# CellsVoltMeasurementSensor.net
KiCad netlist of a schematic drawn in Altium Designer
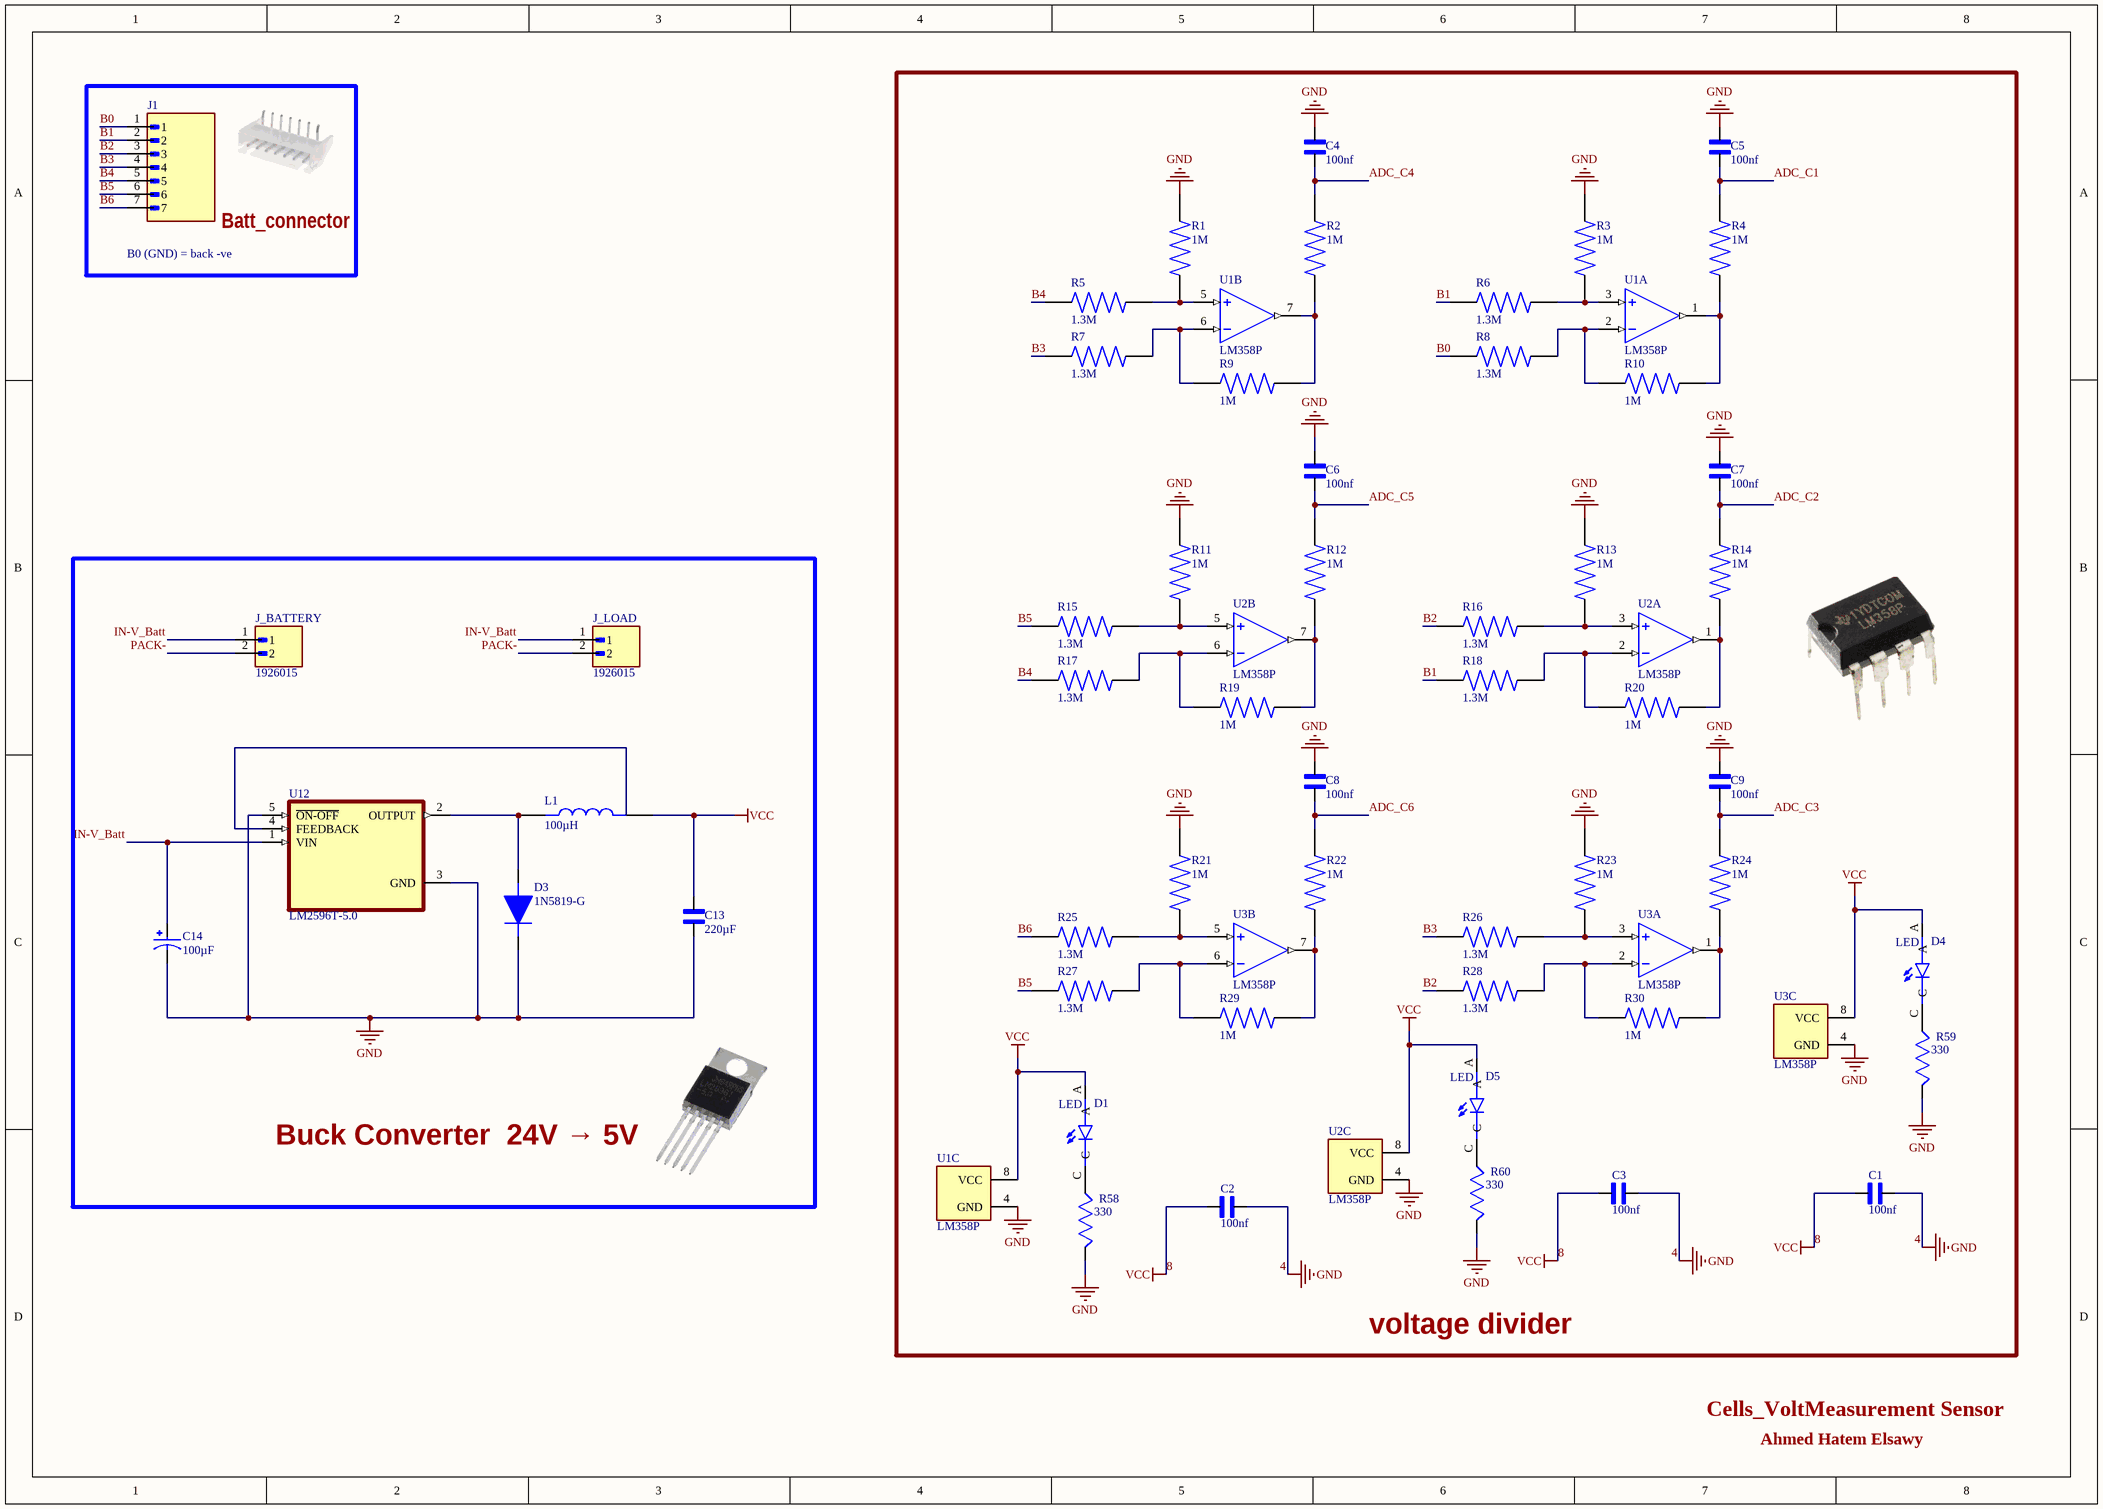
[diagram p0: CellsVoltMeasurementSensor.SchDoc]

(export (version "E")
  (design (tool "Eeschema 10.0.6"))
  (components
    (comp (ref "C1")
      (value "100nf")
      (footprint "CAPC1608X90N")
      (description "Capacitor MLCC 0603 100nF 50V ¦ AVX 06035C104K4T2A")
      (fields (field (name "MF") "AVX") (field (name "MP") "06035C104K4T2A"))
      (libsource (lib "") (part "06035C104K4T2A_1"))
    )
    (comp (ref "C2")
      (value "100nf")
      (footprint "CAPC1608X90N")
      (description "Capacitor MLCC 0603 100nF 50V ¦ AVX 06035C104K4T2A")
      (fields (field (name "MF") "AVX") (field (name "MP") "06035C104K4T2A"))
      (libsource (lib "") (part "06035C104K4T2A_1"))
    )
    (comp (ref "C3")
      (value "100nf")
      (footprint "CAPC1608X90N")
      (description "Capacitor MLCC 0603 100nF 50V ¦ AVX 06035C104K4T2A")
      (fields (field (name "MF") "AVX") (field (name "MP") "06035C104K4T2A"))
      (libsource (lib "") (part "06035C104K4T2A_1"))
    )
    (comp (ref "C4")
      (value "100nf")
      (footprint "CAPC1608X90N")
      (description "Capacitor MLCC 0603 100nF 50V ¦ AVX 06035C104K4T2A")
      (fields (field (name "MF") "AVX") (field (name "MP") "06035C104K4T2A"))
      (libsource (lib "06035C104K4T2A") (part "06035C104K4T2A"))
    )
    (comp (ref "C5")
      (value "100nf")
      (footprint "CAPC1608X90N")
      (description "Capacitor MLCC 0603 100nF 50V ¦ AVX 06035C104K4T2A")
      (fields (field (name "MF") "AVX") (field (name "MP") "06035C104K4T2A"))
      (libsource (lib "06035C104K4T2A") (part "06035C104K4T2A"))
    )
    (comp (ref "C6")
      (value "100nf")
      (footprint "CAPC1608X90N")
      (description "Capacitor MLCC 0603 100nF 50V ¦ AVX 06035C104K4T2A")
      (fields (field (name "MF") "AVX") (field (name "MP") "06035C104K4T2A"))
      (libsource (lib "06035C104K4T2A") (part "06035C104K4T2A"))
    )
    (comp (ref "C7")
      (value "100nf")
      (footprint "CAPC1608X90N")
      (description "Capacitor MLCC 0603 100nF 50V ¦ AVX 06035C104K4T2A")
      (fields (field (name "MF") "AVX") (field (name "MP") "06035C104K4T2A"))
      (libsource (lib "06035C104K4T2A") (part "06035C104K4T2A"))
    )
    (comp (ref "C8")
      (value "100nf")
      (footprint "CAPC1608X90N")
      (description "Capacitor MLCC 0603 100nF 50V ¦ AVX 06035C104K4T2A")
      (fields (field (name "MF") "AVX") (field (name "MP") "06035C104K4T2A"))
      (libsource (lib "06035C104K4T2A") (part "06035C104K4T2A"))
    )
    (comp (ref "C9")
      (value "100nf")
      (footprint "CAPC1608X90N")
      (description "Capacitor MLCC 0603 100nF 50V ¦ AVX 06035C104K4T2A")
      (fields (field (name "MF") "AVX") (field (name "MP") "06035C104K4T2A"))
      (libsource (lib "06035C104K4T2A") (part "06035C104K4T2A"))
    )
    (comp (ref "C13")
      (value "220µF")
      (footprint "CAPPM7343X310N")
      (description "Capacitor;Tantalum;220uF;Tol 10%;SMT;Vol-Rtg 10V;Size 7343-43 ¦ Sprague / Vishay 593D227X9010E2TE3")
      (fields (field (name "MF") "Vishay Sprague") (field (name "MP") "593D227X9010E2TE3"))
      (libsource (lib "593D227X9010E2TE3") (part "593D227X9010E2TE3"))
    )
    (comp (ref "C14")
      (value "100µF")
      (footprint "CAP_EEEFN1E101UP")
      (description "CAP ALUM 100UF 20% 25V SMD")
      (fields (field (name "MF") "Panasonic") (field (name "MP") "EEEFN1E101UP"))
      (libsource (lib "EEEFN1E101UP") (part "EEEFN1E101UP"))
    )
    (comp (ref "D1")
      (value "LED")
      (footprint "LED_WP7113ID")
      (description "Red 617nm LED Indication - Discrete 2V Radial")
      (fields (field (name "MP") "WP7113ID") (field (name "MF") "Kingbright"))
      (libsource (lib "WP7113ID") (part "WP7113ID"))
    )
    (comp (ref "D3")
      (value "1N5819-G")
      (footprint "DIOAD1405W75L465D235")
      (fields (field (name "MF") "ON Semiconductor") (field (name "MP") "1N5819G"))
      (libsource (lib "1N5819-G") (part "1N5819-G"))
    )
    (comp (ref "D4")
      (value "LED")
      (footprint "LED_WP7113ID")
      (description "Red 617nm LED Indication - Discrete 2V Radial")
      (fields (field (name "MP") "WP7113ID") (field (name "MF") "Kingbright"))
      (libsource (lib "WP7113ID") (part "WP7113ID"))
    )
    (comp (ref "D5")
      (value "LED")
      (footprint "LED_WP7113ID")
      (description "Red 617nm LED Indication - Discrete 2V Radial")
      (fields (field (name "MP") "WP7113ID") (field (name "MF") "Kingbright"))
      (libsource (lib "WP7113ID") (part "WP7113ID"))
    )
    (comp (ref "J1")
      (value "S7B-XH-A(LF)(SN)")
      (footprint "JST_S7B-XH-A(LF)(SN)")
      (description "Connector Header Through Hole, Right Angle 7 position 0.098 (2.50mm)")
      (fields (field (name "MF") "JST Sales"))
      (libsource (lib "S7B-XH-A_LF__SN_") (part "S7B-XH-A(LF)(SN)"))
    )
    (comp (ref "J_BATTERY")
      (value "1926015")
      (footprint "PHOENIX_1926015")
      (libsource (lib "1926015") (part "1926015"))
    )
    (comp (ref "J_LOAD")
      (value "1926015")
      (footprint "PHOENIX_1926015")
      (libsource (lib "1926015") (part "1926015"))
    )
    (comp (ref "L1")
      (value "100µH")
      (footprint "INDC2012X145N")
      (description "100ÂµH Shielded Multilayer Inductor 2mA 3.1Ohm Max 0805 (2012 Metric)")
      (fields (field (name "MF") "TDK") (field (name "MP") "MLF2012C101MTD25"))
      (libsource (lib "MLF2012C101MTD25") (part "MLF2012C101MTD25"))
    )
    (comp (ref "R1")
      (value "1M")
      (footprint "RESC3216X75N")
      (description "Res 1206 1M 1% 250mW ¦ Bourns CR1206-FX-1004ELF")
      (fields (field (name "MF") "Bourns") (field (name "MP") "CR1206-FX-1004ELF"))
      (libsource (lib "CR1206-FX-1004ELF") (part "CR1206-FX-1004ELF"))
    )
    (comp (ref "R2")
      (value "1M")
      (footprint "RESC3216X75N")
      (description "Res 1206 1M 1% 250mW ¦ Bourns CR1206-FX-1004ELF")
      (fields (field (name "MF") "Bourns") (field (name "MP") "CR1206-FX-1004ELF"))
      (libsource (lib "CR1206-FX-1004ELF") (part "CR1206-FX-1004ELF"))
    )
    (comp (ref "R3")
      (value "1M")
      (footprint "RESC3216X75N")
      (description "Res 1206 1M 1% 250mW ¦ Bourns CR1206-FX-1004ELF")
      (fields (field (name "MF") "Bourns") (field (name "MP") "CR1206-FX-1004ELF"))
      (libsource (lib "CR1206-FX-1004ELF") (part "CR1206-FX-1004ELF"))
    )
    (comp (ref "R4")
      (value "1M")
      (footprint "RESC3216X75N")
      (description "Res 1206 1M 1% 250mW ¦ Bourns CR1206-FX-1004ELF")
      (fields (field (name "MF") "Bourns") (field (name "MP") "CR1206-FX-1004ELF"))
      (libsource (lib "CR1206-FX-1004ELF") (part "CR1206-FX-1004ELF"))
    )
    (comp (ref "R5")
      (value "1.3M")
      (footprint "RESC5025X70N")
      (description "Res Thick Film 2010 1.3M Ohm 5% 3/4W -400ppm/Â°C to 150ppm/Â°C Molded SMD SMD Embossed Carrier T/R")
      (fields (field (name "MF") "Panasonic") (field (name "MP") "ERJ-12ZYJ135U"))
      (libsource (lib "ERJ-12ZYJ135U") (part "ERJ-12ZYJ135U"))
    )
    (comp (ref "R6")
      (value "1.3M")
      (footprint "RESC5025X70N")
      (description "Res Thick Film 2010 1.3M Ohm 5% 3/4W -400ppm/Â°C to 150ppm/Â°C Molded SMD SMD Embossed Carrier T/R")
      (fields (field (name "MF") "Panasonic") (field (name "MP") "ERJ-12ZYJ135U"))
      (libsource (lib "ERJ-12ZYJ135U") (part "ERJ-12ZYJ135U"))
    )
    (comp (ref "R7")
      (value "1.3M")
      (footprint "RESC5025X70N")
      (description "Res Thick Film 2010 1.3M Ohm 5% 3/4W -400ppm/Â°C to 150ppm/Â°C Molded SMD SMD Embossed Carrier T/R")
      (fields (field (name "MF") "Panasonic") (field (name "MP") "ERJ-12ZYJ135U"))
      (libsource (lib "ERJ-12ZYJ135U") (part "ERJ-12ZYJ135U"))
    )
    (comp (ref "R8")
      (value "1.3M")
      (footprint "RESC5025X70N")
      (description "Res Thick Film 2010 1.3M Ohm 5% 3/4W -400ppm/Â°C to 150ppm/Â°C Molded SMD SMD Embossed Carrier T/R")
      (fields (field (name "MF") "Panasonic") (field (name "MP") "ERJ-12ZYJ135U"))
      (libsource (lib "ERJ-12ZYJ135U") (part "ERJ-12ZYJ135U"))
    )
    (comp (ref "R9")
      (value "1M")
      (footprint "RESC3216X75N")
      (description "Res 1206 1M 1% 250mW ¦ Bourns CR1206-FX-1004ELF")
      (fields (field (name "MF") "Bourns") (field (name "MP") "CR1206-FX-1004ELF"))
      (libsource (lib "CR1206-FX-1004ELF") (part "CR1206-FX-1004ELF"))
    )
    (comp (ref "R10")
      (value "1M")
      (footprint "RESC3216X75N")
      (description "Res 1206 1M 1% 250mW ¦ Bourns CR1206-FX-1004ELF")
      (fields (field (name "MF") "Bourns") (field (name "MP") "CR1206-FX-1004ELF"))
      (libsource (lib "CR1206-FX-1004ELF") (part "CR1206-FX-1004ELF"))
    )
    (comp (ref "R11")
      (value "1M")
      (footprint "RESC3216X75N")
      (description "Res 1206 1M 1% 250mW ¦ Bourns CR1206-FX-1004ELF")
      (fields (field (name "MF") "Bourns") (field (name "MP") "CR1206-FX-1004ELF"))
      (libsource (lib "CR1206-FX-1004ELF") (part "CR1206-FX-1004ELF"))
    )
    (comp (ref "R12")
      (value "1M")
      (footprint "RESC3216X75N")
      (description "Res 1206 1M 1% 250mW ¦ Bourns CR1206-FX-1004ELF")
      (fields (field (name "MF") "Bourns") (field (name "MP") "CR1206-FX-1004ELF"))
      (libsource (lib "CR1206-FX-1004ELF") (part "CR1206-FX-1004ELF"))
    )
    (comp (ref "R13")
      (value "1M")
      (footprint "RESC3216X75N")
      (description "Res 1206 1M 1% 250mW ¦ Bourns CR1206-FX-1004ELF")
      (fields (field (name "MF") "Bourns") (field (name "MP") "CR1206-FX-1004ELF"))
      (libsource (lib "CR1206-FX-1004ELF") (part "CR1206-FX-1004ELF"))
    )
    (comp (ref "R14")
      (value "1M")
      (footprint "RESC3216X75N")
      (description "Res 1206 1M 1% 250mW ¦ Bourns CR1206-FX-1004ELF")
      (fields (field (name "MF") "Bourns") (field (name "MP") "CR1206-FX-1004ELF"))
      (libsource (lib "CR1206-FX-1004ELF") (part "CR1206-FX-1004ELF"))
    )
    (comp (ref "R15")
      (value "1.3M")
      (footprint "RESC5025X70N")
      (description "Res Thick Film 2010 1.3M Ohm 5% 3/4W -400ppm/Â°C to 150ppm/Â°C Molded SMD SMD Embossed Carrier T/R")
      (fields (field (name "MF") "Panasonic") (field (name "MP") "ERJ-12ZYJ135U"))
      (libsource (lib "ERJ-12ZYJ135U") (part "ERJ-12ZYJ135U"))
    )
    (comp (ref "R16")
      (value "1.3M")
      (footprint "RESC5025X70N")
      (description "Res Thick Film 2010 1.3M Ohm 5% 3/4W -400ppm/Â°C to 150ppm/Â°C Molded SMD SMD Embossed Carrier T/R")
      (fields (field (name "MF") "Panasonic") (field (name "MP") "ERJ-12ZYJ135U"))
      (libsource (lib "ERJ-12ZYJ135U") (part "ERJ-12ZYJ135U"))
    )
    (comp (ref "R17")
      (value "1.3M")
      (footprint "RESC5025X70N")
      (description "Res Thick Film 2010 1.3M Ohm 5% 3/4W -400ppm/Â°C to 150ppm/Â°C Molded SMD SMD Embossed Carrier T/R")
      (fields (field (name "MF") "Panasonic") (field (name "MP") "ERJ-12ZYJ135U"))
      (libsource (lib "ERJ-12ZYJ135U") (part "ERJ-12ZYJ135U"))
    )
    (comp (ref "R18")
      (value "1.3M")
      (footprint "RESC5025X70N")
      (description "Res Thick Film 2010 1.3M Ohm 5% 3/4W -400ppm/Â°C to 150ppm/Â°C Molded SMD SMD Embossed Carrier T/R")
      (fields (field (name "MF") "Panasonic") (field (name "MP") "ERJ-12ZYJ135U"))
      (libsource (lib "ERJ-12ZYJ135U") (part "ERJ-12ZYJ135U"))
    )
    (comp (ref "R19")
      (value "1M")
      (footprint "RESC3216X75N")
      (description "Res 1206 1M 1% 250mW ¦ Bourns CR1206-FX-1004ELF")
      (fields (field (name "MF") "Bourns") (field (name "MP") "CR1206-FX-1004ELF"))
      (libsource (lib "CR1206-FX-1004ELF") (part "CR1206-FX-1004ELF"))
    )
    (comp (ref "R20")
      (value "1M")
      (footprint "RESC3216X75N")
      (description "Res 1206 1M 1% 250mW ¦ Bourns CR1206-FX-1004ELF")
      (fields (field (name "MF") "Bourns") (field (name "MP") "CR1206-FX-1004ELF"))
      (libsource (lib "CR1206-FX-1004ELF") (part "CR1206-FX-1004ELF"))
    )
    (comp (ref "R21")
      (value "1M")
      (footprint "RESC3216X75N")
      (description "Res 1206 1M 1% 250mW ¦ Bourns CR1206-FX-1004ELF")
      (fields (field (name "MF") "Bourns") (field (name "MP") "CR1206-FX-1004ELF"))
      (libsource (lib "CR1206-FX-1004ELF") (part "CR1206-FX-1004ELF"))
    )
    (comp (ref "R22")
      (value "1M")
      (footprint "RESC3216X75N")
      (description "Res 1206 1M 1% 250mW ¦ Bourns CR1206-FX-1004ELF")
      (fields (field (name "MF") "Bourns") (field (name "MP") "CR1206-FX-1004ELF"))
      (libsource (lib "CR1206-FX-1004ELF") (part "CR1206-FX-1004ELF"))
    )
    (comp (ref "R23")
      (value "1M")
      (footprint "RESC3216X75N")
      (description "Res 1206 1M 1% 250mW ¦ Bourns CR1206-FX-1004ELF")
      (fields (field (name "MF") "Bourns") (field (name "MP") "CR1206-FX-1004ELF"))
      (libsource (lib "CR1206-FX-1004ELF") (part "CR1206-FX-1004ELF"))
    )
    (comp (ref "R24")
      (value "1M")
      (footprint "RESC3216X75N")
      (description "Res 1206 1M 1% 250mW ¦ Bourns CR1206-FX-1004ELF")
      (fields (field (name "MF") "Bourns") (field (name "MP") "CR1206-FX-1004ELF"))
      (libsource (lib "CR1206-FX-1004ELF") (part "CR1206-FX-1004ELF"))
    )
    (comp (ref "R25")
      (value "1.3M")
      (footprint "RESC5025X70N")
      (description "Res Thick Film 2010 1.3M Ohm 5% 3/4W -400ppm/Â°C to 150ppm/Â°C Molded SMD SMD Embossed Carrier T/R")
      (fields (field (name "MF") "Panasonic") (field (name "MP") "ERJ-12ZYJ135U"))
      (libsource (lib "ERJ-12ZYJ135U") (part "ERJ-12ZYJ135U"))
    )
    (comp (ref "R26")
      (value "1.3M")
      (footprint "RESC5025X70N")
      (description "Res Thick Film 2010 1.3M Ohm 5% 3/4W -400ppm/Â°C to 150ppm/Â°C Molded SMD SMD Embossed Carrier T/R")
      (fields (field (name "MF") "Panasonic") (field (name "MP") "ERJ-12ZYJ135U"))
      (libsource (lib "ERJ-12ZYJ135U") (part "ERJ-12ZYJ135U"))
    )
    (comp (ref "R27")
      (value "1.3M")
      (footprint "RESC5025X70N")
      (description "Res Thick Film 2010 1.3M Ohm 5% 3/4W -400ppm/Â°C to 150ppm/Â°C Molded SMD SMD Embossed Carrier T/R")
      (fields (field (name "MF") "Panasonic") (field (name "MP") "ERJ-12ZYJ135U"))
      (libsource (lib "ERJ-12ZYJ135U") (part "ERJ-12ZYJ135U"))
    )
    (comp (ref "R28")
      (value "1.3M")
      (footprint "RESC5025X70N")
      (description "Res Thick Film 2010 1.3M Ohm 5% 3/4W -400ppm/Â°C to 150ppm/Â°C Molded SMD SMD Embossed Carrier T/R")
      (fields (field (name "MF") "Panasonic") (field (name "MP") "ERJ-12ZYJ135U"))
      (libsource (lib "ERJ-12ZYJ135U") (part "ERJ-12ZYJ135U"))
    )
    (comp (ref "R29")
      (value "1M")
      (footprint "RESC3216X75N")
      (description "Res 1206 1M 1% 250mW ¦ Bourns CR1206-FX-1004ELF")
      (fields (field (name "MF") "Bourns") (field (name "MP") "CR1206-FX-1004ELF"))
      (libsource (lib "CR1206-FX-1004ELF") (part "CR1206-FX-1004ELF"))
    )
    (comp (ref "R30")
      (value "1M")
      (footprint "RESC3216X75N")
      (description "Res 1206 1M 1% 250mW ¦ Bourns CR1206-FX-1004ELF")
      (fields (field (name "MF") "Bourns") (field (name "MP") "CR1206-FX-1004ELF"))
      (libsource (lib "CR1206-FX-1004ELF") (part "CR1206-FX-1004ELF"))
    )
    (comp (ref "R58")
      (value "330")
      (footprint "RESC3216X65")
      (description "Res Thick Film 1206 330 Ohm 5% 0.25W(1/4W) Â±100ppm/Â°C Epoxy Pad SMD T/R")
      (fields (field (name "MF") "Yageo Corporation") (field (name "MP") "RC1206JR13330RL"))
      (libsource (lib "RC1206JR-13330RL") (part "RC1206JR-13330RL"))
    )
    (comp (ref "R59")
      (value "330")
      (footprint "RESC3216X65")
      (description "Res Thick Film 1206 330 Ohm 5% 0.25W(1/4W) Â±100ppm/Â°C Epoxy Pad SMD T/R")
      (fields (field (name "MF") "Yageo Corporation") (field (name "MP") "RC1206JR13330RL"))
      (libsource (lib "RC1206JR-13330RL") (part "RC1206JR-13330RL"))
    )
    (comp (ref "R60")
      (value "330")
      (footprint "RESC3216X65")
      (description "Res Thick Film 1206 330 Ohm 5% 0.25W(1/4W) Â±100ppm/Â°C Epoxy Pad SMD T/R")
      (fields (field (name "MF") "Yageo Corporation") (field (name "MP") "RC1206JR13330RL"))
      (libsource (lib "RC1206JR-13330RL") (part "RC1206JR-13330RL"))
    )
    (comp (ref "U1")
      (value "LM358P")
      (footprint "DIP794W45P254L959H508Q8")
      (description "Dual, 30-V, 700-kHz operational amplifier")
      (fields (field (name "MF") "Texas Instruments"))
      (libsource (lib "LM358P") (part "LM358P"))
    )
    (comp (ref "U2")
      (value "LM358P")
      (footprint "DIP794W45P254L959H508Q8")
      (description "Dual, 30-V, 700-kHz operational amplifier")
      (fields (field (name "MF") "Texas Instruments"))
      (libsource (lib "LM358P") (part "LM358P"))
    )
    (comp (ref "U3")
      (value "LM358P")
      (footprint "DIP794W45P254L959H508Q8")
      (description "Dual, 30-V, 700-kHz operational amplifier")
      (fields (field (name "MF") "Texas Instruments"))
      (libsource (lib "LM358P") (part "LM358P"))
    )
    (comp (ref "U12")
      (value "LM2596T-5.0")
      (footprint "TO170P1016X470X2092-5")
      (description "SIMPLE SWITCHERÂ® 4.5V to 40V, 3A Low Component Count Step-Down Regulator 5-TO-220")
      (fields (field (name "MF") "Texas Instruments"))
      (libsource (lib "LM2596T-5.0") (part "LM2596T-5.0"))
    )
  )
  (nets
    (net (code "1") (name "/ADC_C1") (class "Default")
      (node (ref "C5") (pin "1") (pinfunction "1_1") (pintype "passive"))
      (node (ref "R4") (pin "2") (pinfunction "2_2") (pintype "passive"))
    )
    (net (code "2") (name "/ADC_C2") (class "Default")
      (node (ref "C7") (pin "1") (pinfunction "1_1") (pintype "passive"))
      (node (ref "R14") (pin "2") (pinfunction "2_2") (pintype "passive"))
    )
    (net (code "3") (name "/ADC_C3") (class "Default")
      (node (ref "C9") (pin "1") (pinfunction "1_1") (pintype "passive"))
      (node (ref "R24") (pin "2") (pinfunction "2_2") (pintype "passive"))
    )
    (net (code "4") (name "/ADC_C4") (class "Default")
      (node (ref "C4") (pin "1") (pinfunction "1_1") (pintype "passive"))
      (node (ref "R2") (pin "2") (pinfunction "2_2") (pintype "passive"))
    )
    (net (code "5") (name "/ADC_C5") (class "Default")
      (node (ref "C6") (pin "1") (pinfunction "1_1") (pintype "passive"))
      (node (ref "R12") (pin "2") (pinfunction "2_2") (pintype "passive"))
    )
    (net (code "6") (name "/ADC_C6") (class "Default")
      (node (ref "C8") (pin "1") (pinfunction "1_1") (pintype "passive"))
      (node (ref "R22") (pin "2") (pinfunction "2_2") (pintype "passive"))
    )
    (net (code "7") (name "/B0") (class "Default")
      (node (ref "J1") (pin "1") (pinfunction "1_1") (pintype "passive"))
      (node (ref "R8") (pin "1") (pinfunction "1_1") (pintype "passive"))
    )
    (net (code "8") (name "/B1") (class "Default")
      (node (ref "J1") (pin "2") (pinfunction "2_2") (pintype "passive"))
      (node (ref "R18") (pin "1") (pinfunction "1_1") (pintype "passive"))
      (node (ref "R6") (pin "1") (pinfunction "1_1") (pintype "passive"))
    )
    (net (code "9") (name "/B2") (class "Default")
      (node (ref "J1") (pin "3") (pinfunction "3_3") (pintype "passive"))
      (node (ref "R16") (pin "1") (pinfunction "1_1") (pintype "passive"))
      (node (ref "R28") (pin "1") (pinfunction "1_1") (pintype "passive"))
    )
    (net (code "10") (name "/B3") (class "Default")
      (node (ref "J1") (pin "4") (pinfunction "4_4") (pintype "passive"))
      (node (ref "R26") (pin "1") (pinfunction "1_1") (pintype "passive"))
      (node (ref "R7") (pin "1") (pinfunction "1_1") (pintype "passive"))
    )
    (net (code "11") (name "/B4") (class "Default")
      (node (ref "J1") (pin "5") (pinfunction "5_5") (pintype "passive"))
      (node (ref "R17") (pin "1") (pinfunction "1_1") (pintype "passive"))
      (node (ref "R5") (pin "1") (pinfunction "1_1") (pintype "passive"))
    )
    (net (code "12") (name "/B5") (class "Default")
      (node (ref "J1") (pin "6") (pinfunction "6_6") (pintype "passive"))
      (node (ref "R15") (pin "1") (pinfunction "1_1") (pintype "passive"))
      (node (ref "R27") (pin "1") (pinfunction "1_1") (pintype "passive"))
    )
    (net (code "13") (name "/B6") (class "Default")
      (node (ref "J1") (pin "7") (pinfunction "7_7") (pintype "passive"))
      (node (ref "R25") (pin "1") (pinfunction "1_1") (pintype "passive"))
    )
    (net (code "14") (name "/IN-V_Batt") (class "Default")
      (node (ref "C14") (pin "1") (pinfunction "1_1") (pintype "passive"))
      (node (ref "J_BATTERY") (pin "1") (pinfunction "1_1") (pintype "passive"))
      (node (ref "J_LOAD") (pin "1") (pinfunction "1_1") (pintype "passive"))
      (node (ref "U12") (pin "1") (pinfunction "VIN_1") (pintype "input"))
    )
    (net (code "15") (name "/PACK-") (class "Default")
      (node (ref "J_BATTERY") (pin "2") (pinfunction "2_2") (pintype "passive"))
      (node (ref "J_LOAD") (pin "2") (pinfunction "2_2") (pintype "passive"))
    )
    (net (code "16") (name "GND") (class "Default")
      (node (ref "C1") (pin "1") (pinfunction "1_1") (pintype "passive"))
      (node (ref "C13") (pin "1") (pinfunction "1_1") (pintype "passive"))
      (node (ref "C14") (pin "2") (pinfunction "2_2") (pintype "passive"))
      (node (ref "C2") (pin "1") (pinfunction "1_1") (pintype "passive"))
      (node (ref "C3") (pin "1") (pinfunction "1_1") (pintype "passive"))
      (node (ref "C4") (pin "2") (pinfunction "2_2") (pintype "passive"))
      (node (ref "C5") (pin "2") (pinfunction "2_2") (pintype "passive"))
      (node (ref "C6") (pin "2") (pinfunction "2_2") (pintype "passive"))
      (node (ref "C7") (pin "2") (pinfunction "2_2") (pintype "passive"))
      (node (ref "C8") (pin "2") (pinfunction "2_2") (pintype "passive"))
      (node (ref "C9") (pin "2") (pinfunction "2_2") (pintype "passive"))
      (node (ref "D3") (pin "1") (pinfunction "K_1") (pintype "bidirectional"))
      (node (ref "R1") (pin "2") (pinfunction "2_2") (pintype "passive"))
      (node (ref "R11") (pin "2") (pinfunction "2_2") (pintype "passive"))
      (node (ref "R13") (pin "2") (pinfunction "2_2") (pintype "passive"))
      (node (ref "R21") (pin "2") (pinfunction "2_2") (pintype "passive"))
      (node (ref "R23") (pin "2") (pinfunction "2_2") (pintype "passive"))
      (node (ref "R3") (pin "2") (pinfunction "2_2") (pintype "passive"))
      (node (ref "R58") (pin "1") (pinfunction "1_1") (pintype "passive"))
      (node (ref "R59") (pin "1") (pinfunction "1_1") (pintype "passive"))
      (node (ref "R60") (pin "1") (pinfunction "1_1") (pintype "passive"))
      (node (ref "U1") (pin "4") (pinfunction "GND_4") (pintype "power_in"))
      (node (ref "U12") (pin "3") (pinfunction "GND_3") (pintype "power_in"))
      (node (ref "U12") (pin "5") (pinfunction "~{ON-OFF}_5") (pintype "input"))
      (node (ref "U2") (pin "4") (pinfunction "GND_4") (pintype "power_in"))
      (node (ref "U3") (pin "4") (pinfunction "GND_4") (pintype "power_in"))
    )
    (net (code "17") (name "Net-(D1-PadC)") (class "Default")
      (node (ref "D1") (pin "C") (pinfunction "C_C") (pintype "passive"))
      (node (ref "R58") (pin "2") (pinfunction "2_2") (pintype "passive"))
    )
    (net (code "18") (name "Net-(D3-A)") (class "Default")
      (node (ref "D3") (pin "2") (pinfunction "A_2") (pintype "bidirectional"))
      (node (ref "L1") (pin "1") (pinfunction "1_1") (pintype "passive"))
      (node (ref "U12") (pin "2") (pinfunction "OUTPUT_2") (pintype "output"))
    )
    (net (code "19") (name "Net-(D4-PadC)") (class "Default")
      (node (ref "D4") (pin "C") (pinfunction "C_C") (pintype "passive"))
      (node (ref "R59") (pin "2") (pinfunction "2_2") (pintype "passive"))
    )
    (net (code "20") (name "Net-(D5-PadC)") (class "Default")
      (node (ref "D5") (pin "C") (pinfunction "C_C") (pintype "passive"))
      (node (ref "R60") (pin "2") (pinfunction "2_2") (pintype "passive"))
    )
    (net (code "21") (name "Net-(U1A-+IN1)") (class "Default")
      (node (ref "R3") (pin "1") (pinfunction "1_1") (pintype "passive"))
      (node (ref "R6") (pin "2") (pinfunction "2_2") (pintype "passive"))
      (node (ref "U1") (pin "3") (pinfunction "+IN1_3") (pintype "input"))
    )
    (net (code "22") (name "Net-(U1A--IN1)") (class "Default")
      (node (ref "R10") (pin "1") (pinfunction "1_1") (pintype "passive"))
      (node (ref "R8") (pin "2") (pinfunction "2_2") (pintype "passive"))
      (node (ref "U1") (pin "2") (pinfunction "-IN1_2") (pintype "input"))
    )
    (net (code "23") (name "Net-(U1A-OUT1)") (class "Default")
      (node (ref "R10") (pin "2") (pinfunction "2_2") (pintype "passive"))
      (node (ref "R4") (pin "1") (pinfunction "1_1") (pintype "passive"))
      (node (ref "U1") (pin "1") (pinfunction "OUT1_1") (pintype "output"))
    )
    (net (code "24") (name "Net-(U1B-+IN2)") (class "Default")
      (node (ref "R1") (pin "1") (pinfunction "1_1") (pintype "passive"))
      (node (ref "R5") (pin "2") (pinfunction "2_2") (pintype "passive"))
      (node (ref "U1") (pin "5") (pinfunction "+IN2_5") (pintype "input"))
    )
    (net (code "25") (name "Net-(U1B--IN2)") (class "Default")
      (node (ref "R7") (pin "2") (pinfunction "2_2") (pintype "passive"))
      (node (ref "R9") (pin "1") (pinfunction "1_1") (pintype "passive"))
      (node (ref "U1") (pin "6") (pinfunction "-IN2_6") (pintype "input"))
    )
    (net (code "26") (name "Net-(U1B-OUT2)") (class "Default")
      (node (ref "R2") (pin "1") (pinfunction "1_1") (pintype "passive"))
      (node (ref "R9") (pin "2") (pinfunction "2_2") (pintype "passive"))
      (node (ref "U1") (pin "7") (pinfunction "OUT2_7") (pintype "output"))
    )
    (net (code "27") (name "Net-(U2A-+IN1)") (class "Default")
      (node (ref "R13") (pin "1") (pinfunction "1_1") (pintype "passive"))
      (node (ref "R16") (pin "2") (pinfunction "2_2") (pintype "passive"))
      (node (ref "U2") (pin "3") (pinfunction "+IN1_3") (pintype "input"))
    )
    (net (code "28") (name "Net-(U2A--IN1)") (class "Default")
      (node (ref "R18") (pin "2") (pinfunction "2_2") (pintype "passive"))
      (node (ref "R20") (pin "1") (pinfunction "1_1") (pintype "passive"))
      (node (ref "U2") (pin "2") (pinfunction "-IN1_2") (pintype "input"))
    )
    (net (code "29") (name "Net-(U2A-OUT1)") (class "Default")
      (node (ref "R14") (pin "1") (pinfunction "1_1") (pintype "passive"))
      (node (ref "R20") (pin "2") (pinfunction "2_2") (pintype "passive"))
      (node (ref "U2") (pin "1") (pinfunction "OUT1_1") (pintype "output"))
    )
    (net (code "30") (name "Net-(U2B-+IN2)") (class "Default")
      (node (ref "R11") (pin "1") (pinfunction "1_1") (pintype "passive"))
      (node (ref "R15") (pin "2") (pinfunction "2_2") (pintype "passive"))
      (node (ref "U2") (pin "5") (pinfunction "+IN2_5") (pintype "input"))
    )
    (net (code "31") (name "Net-(U2B--IN2)") (class "Default")
      (node (ref "R17") (pin "2") (pinfunction "2_2") (pintype "passive"))
      (node (ref "R19") (pin "1") (pinfunction "1_1") (pintype "passive"))
      (node (ref "U2") (pin "6") (pinfunction "-IN2_6") (pintype "input"))
    )
    (net (code "32") (name "Net-(U2B-OUT2)") (class "Default")
      (node (ref "R12") (pin "1") (pinfunction "1_1") (pintype "passive"))
      (node (ref "R19") (pin "2") (pinfunction "2_2") (pintype "passive"))
      (node (ref "U2") (pin "7") (pinfunction "OUT2_7") (pintype "output"))
    )
    (net (code "33") (name "Net-(U3A-+IN1)") (class "Default")
      (node (ref "R23") (pin "1") (pinfunction "1_1") (pintype "passive"))
      (node (ref "R26") (pin "2") (pinfunction "2_2") (pintype "passive"))
      (node (ref "U3") (pin "3") (pinfunction "+IN1_3") (pintype "input"))
    )
    (net (code "34") (name "Net-(U3A--IN1)") (class "Default")
      (node (ref "R28") (pin "2") (pinfunction "2_2") (pintype "passive"))
      (node (ref "R30") (pin "1") (pinfunction "1_1") (pintype "passive"))
      (node (ref "U3") (pin "2") (pinfunction "-IN1_2") (pintype "input"))
    )
    (net (code "35") (name "Net-(U3A-OUT1)") (class "Default")
      (node (ref "R24") (pin "1") (pinfunction "1_1") (pintype "passive"))
      (node (ref "R30") (pin "2") (pinfunction "2_2") (pintype "passive"))
      (node (ref "U3") (pin "1") (pinfunction "OUT1_1") (pintype "output"))
    )
    (net (code "36") (name "Net-(U3B-+IN2)") (class "Default")
      (node (ref "R21") (pin "1") (pinfunction "1_1") (pintype "passive"))
      (node (ref "R25") (pin "2") (pinfunction "2_2") (pintype "passive"))
      (node (ref "U3") (pin "5") (pinfunction "+IN2_5") (pintype "input"))
    )
    (net (code "37") (name "Net-(U3B--IN2)") (class "Default")
      (node (ref "R27") (pin "2") (pinfunction "2_2") (pintype "passive"))
      (node (ref "R29") (pin "1") (pinfunction "1_1") (pintype "passive"))
      (node (ref "U3") (pin "6") (pinfunction "-IN2_6") (pintype "input"))
    )
    (net (code "38") (name "Net-(U3B-OUT2)") (class "Default")
      (node (ref "R22") (pin "1") (pinfunction "1_1") (pintype "passive"))
      (node (ref "R29") (pin "2") (pinfunction "2_2") (pintype "passive"))
      (node (ref "U3") (pin "7") (pinfunction "OUT2_7") (pintype "output"))
    )
    (net (code "39") (name "VCC") (class "Default")
      (node (ref "C1") (pin "2") (pinfunction "2_2") (pintype "passive"))
      (node (ref "C13") (pin "2") (pinfunction "2_2") (pintype "passive"))
      (node (ref "C2") (pin "2") (pinfunction "2_2") (pintype "passive"))
      (node (ref "C3") (pin "2") (pinfunction "2_2") (pintype "passive"))
      (node (ref "D1") (pin "A") (pinfunction "A_A") (pintype "passive"))
      (node (ref "D4") (pin "A") (pinfunction "A_A") (pintype "passive"))
      (node (ref "D5") (pin "A") (pinfunction "A_A") (pintype "passive"))
      (node (ref "L1") (pin "2") (pinfunction "2_2") (pintype "passive"))
      (node (ref "U1") (pin "8") (pinfunction "VCC_8") (pintype "power_in"))
      (node (ref "U2") (pin "8") (pinfunction "VCC_8") (pintype "power_in"))
      (node (ref "U3") (pin "8") (pinfunction "VCC_8") (pintype "power_in"))
    )
    (net (code "40") (name "unconnected-(U12-FEEDBACK-Pad4)") (class "Default")
      (node (ref "U12") (pin "4") (pinfunction "FEEDBACK_4") (pintype "input"))
    )
  )
)
